# main.net
KiCad netlist of a schematic drawn in EAGLE
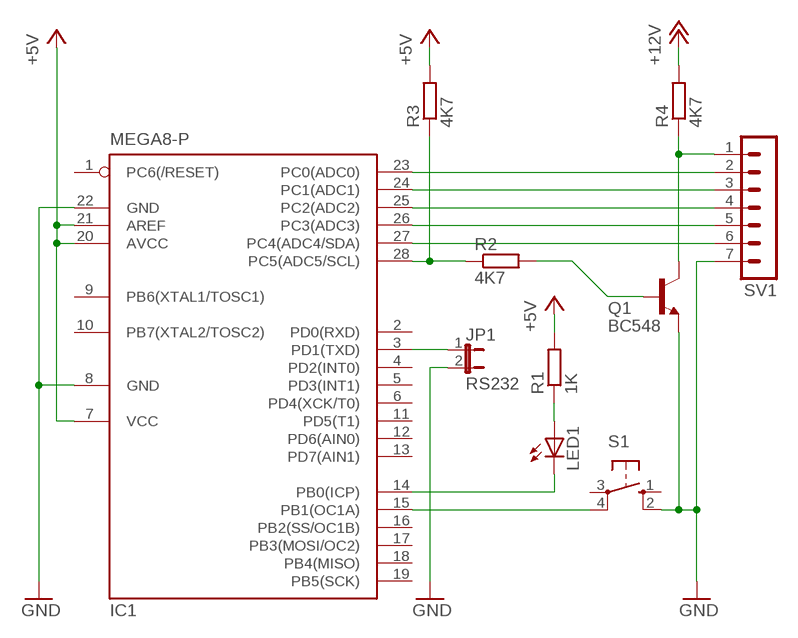
[diagram p0: schematic, sheet 1]
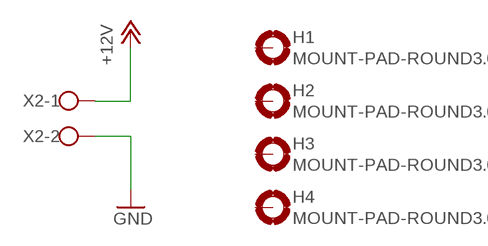
[diagram p1: schematic, sheet 2]
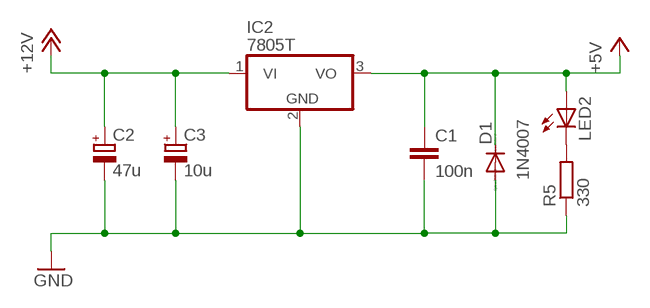
[diagram p2: schematic, sheet 3]

(export (version "E")
  (design (tool "Eeschema 10.0.6"))
  (components
    (comp (ref "IC1")
      (value "MEGA8-P")
      (footprint "eagle-import:DIL28-3")
      (libsource (lib "eagle-import") (part "MEGA8-P"))
    )
    (comp (ref "JP1")
      (value "RS232")
      (footprint "eagle-import:JP1")
      (libsource (lib "eagle-import") (part "JP1E"))
    )
    (comp (ref "LED1")
      (value "LED5MM")
      (footprint "eagle-import:LED5MM")
      (libsource (lib "eagle-import") (part "LED5MM"))
    )
    (comp (ref "Q1")
      (value "BC548")
      (footprint "eagle-import:TO92-EBC")
      (libsource (lib "eagle-import") (part "BC548"))
    )
    (comp (ref "R1")
      (value "1K")
      (footprint "eagle-import:0204_7")
      (libsource (lib "eagle-import") (part "R-EU_0204/7"))
    )
    (comp (ref "R2")
      (value "4K7")
      (footprint "eagle-import:0204_7")
      (libsource (lib "eagle-import") (part "R-EU_0204/7"))
    )
    (comp (ref "R3")
      (value "4K7")
      (footprint "eagle-import:0204_7")
      (libsource (lib "eagle-import") (part "R-EU_0204/7"))
    )
    (comp (ref "R4")
      (value "4K7")
      (footprint "eagle-import:0204_7")
      (libsource (lib "eagle-import") (part "R-EU_0204/7"))
    )
    (comp (ref "S1")
      (value "40-XX")
      (footprint "eagle-import:B3F-40XX")
      (fields (field (name "MF") "OMRON COMPONENTS USA") (field (name "MPN") "B3F-4000"))
      (libsource (lib "eagle-import") (part "40-XX"))
    )
    (comp (ref "SV1")
      (value "MA07-1")
      (footprint "eagle-import:MA07-1")
      (libsource (lib "eagle-import") (part "MA07-1"))
    )
    (comp (ref "H1")
      (value "MOUNT-PAD-ROUND3.0")
      (footprint "eagle-import:3,0-PAD")
      (libsource (lib "eagle-import") (part "MOUNT-PAD-ROUND3.0"))
    )
    (comp (ref "H2")
      (value "MOUNT-PAD-ROUND3.0")
      (footprint "eagle-import:3,0-PAD")
      (libsource (lib "eagle-import") (part "MOUNT-PAD-ROUND3.0"))
    )
    (comp (ref "H3")
      (value "MOUNT-PAD-ROUND3.0")
      (footprint "eagle-import:3,0-PAD")
      (libsource (lib "eagle-import") (part "MOUNT-PAD-ROUND3.0"))
    )
    (comp (ref "H4")
      (value "MOUNT-PAD-ROUND3.0")
      (footprint "eagle-import:3,0-PAD")
      (libsource (lib "eagle-import") (part "MOUNT-PAD-ROUND3.0"))
    )
    (comp (ref "X2")
      (value "W237-102")
      (footprint "eagle-import:W237-102")
      (fields (field (name "MPN") "237-102"))
      (libsource (lib "eagle-import") (part "W237-102"))
    )
    (comp (ref "C1")
      (value "100n")
      (footprint "eagle-import:C025-025X050")
      (libsource (lib "eagle-import") (part "C-EU025-025X050"))
    )
    (comp (ref "C2")
      (value "47u")
      (footprint "eagle-import:E2,5-6")
      (libsource (lib "eagle-import") (part "CPOL-EUE2.5-6"))
    )
    (comp (ref "C3")
      (value "10u")
      (footprint "eagle-import:E2,5-6")
      (libsource (lib "eagle-import") (part "CPOL-EUE2.5-6"))
    )
    (comp (ref "D1")
      (value "1N4007")
      (footprint "eagle-import:D-7.5")
      (libsource (lib "eagle-import") (part "DIODE-D-7.5"))
    )
    (comp (ref "IC2")
      (value "7805T")
      (footprint "eagle-import:TO220H")
      (libsource (lib "eagle-import") (part "78T05"))
    )
    (comp (ref "LED2")
      (value "LED5MM")
      (footprint "eagle-import:LED5MM")
      (libsource (lib "eagle-import") (part "LED5MM"))
    )
    (comp (ref "R5")
      (value "330")
      (footprint "eagle-import:0204_7")
      (libsource (lib "eagle-import") (part "resistor_R-EU_0204/7"))
    )
  )
  (nets
    (net (code "1") (name "+5V") (class "Default")
      (node (ref "C1") (pin "1") (pinfunction "1_1") (pintype "passive"))
      (node (ref "D1") (pin "C") (pinfunction "C_C") (pintype "passive"))
      (node (ref "IC1") (pin "20") (pinfunction "AVCC_20") (pintype "power_in"))
      (node (ref "IC1") (pin "21") (pinfunction "AREF_21") (pintype "passive"))
      (node (ref "IC1") (pin "7") (pinfunction "VCC_7") (pintype "power_in"))
      (node (ref "IC2") (pin "3") (pinfunction "VO_3") (pintype "passive"))
      (node (ref "LED2") (pin "A") (pinfunction "A_A") (pintype "passive"))
      (node (ref "R1") (pin "2") (pinfunction "2_2") (pintype "passive"))
      (node (ref "R3") (pin "2") (pinfunction "2_2") (pintype "passive"))
    )
    (net (code "2") (name "+12V") (class "Default")
      (node (ref "C2") (pin "+") (pinfunction "+_+") (pintype "passive"))
      (node (ref "C3") (pin "+") (pinfunction "+_+") (pintype "passive"))
      (node (ref "IC2") (pin "1") (pinfunction "VI_1") (pintype "input"))
      (node (ref "R4") (pin "2") (pinfunction "2_2") (pintype "passive"))
      (node (ref "X2") (pin "1") (pinfunction "KL_1") (pintype "passive"))
    )
    (net (code "3") (name "GND") (class "Default")
      (node (ref "C1") (pin "2") (pinfunction "2_2") (pintype "passive"))
      (node (ref "C2") (pin "-") (pinfunction "-_-") (pintype "passive"))
      (node (ref "C3") (pin "-") (pinfunction "-_-") (pintype "passive"))
      (node (ref "D1") (pin "A") (pinfunction "A_A") (pintype "passive"))
      (node (ref "IC1") (pin "22") (pinfunction "GND_22") (pintype "power_in"))
      (node (ref "IC1") (pin "8") (pinfunction "GND_8") (pintype "power_in"))
      (node (ref "IC2") (pin "2") (pinfunction "GND_2") (pintype "passive"))
      (node (ref "JP1") (pin "2") (pinfunction "2_2") (pintype "passive"))
      (node (ref "Q1") (pin "E") (pinfunction "E_E") (pintype "passive"))
      (node (ref "R5") (pin "1") (pinfunction "1_1") (pintype "passive"))
      (node (ref "S1") (pin "2") (pinfunction "S1_2") (pintype "passive"))
      (node (ref "SV1") (pin "7") (pinfunction "7_7") (pintype "passive"))
      (node (ref "X2") (pin "2") (pinfunction "KL_2") (pintype "passive"))
    )
    (net (code "4") (name "Net-(IC1-PB0(ICP))") (class "Default")
      (node (ref "IC1") (pin "14") (pinfunction "PB0(ICP)_14") (pintype "bidirectional"))
      (node (ref "LED1") (pin "K") (pinfunction "C_K") (pintype "passive"))
    )
    (net (code "5") (name "Net-(IC1-PB1(OC1A))") (class "Default")
      (node (ref "IC1") (pin "15") (pinfunction "PB1(OC1A)_15") (pintype "bidirectional"))
      (node (ref "S1") (pin "4") (pinfunction "P1_4") (pintype "passive"))
    )
    (net (code "6") (name "Net-(IC1-PC0(ADC0))") (class "Default")
      (node (ref "IC1") (pin "23") (pinfunction "PC0(ADC0)_23") (pintype "bidirectional"))
      (node (ref "SV1") (pin "2") (pinfunction "2_2") (pintype "passive"))
    )
    (net (code "7") (name "Net-(IC1-PC1(ADC1))") (class "Default")
      (node (ref "IC1") (pin "24") (pinfunction "PC1(ADC1)_24") (pintype "bidirectional"))
      (node (ref "SV1") (pin "3") (pinfunction "3_3") (pintype "passive"))
    )
    (net (code "8") (name "Net-(IC1-PC2(ADC2))") (class "Default")
      (node (ref "IC1") (pin "25") (pinfunction "PC2(ADC2)_25") (pintype "bidirectional"))
      (node (ref "SV1") (pin "4") (pinfunction "4_4") (pintype "passive"))
    )
    (net (code "9") (name "Net-(IC1-PC3(ADC3))") (class "Default")
      (node (ref "IC1") (pin "26") (pinfunction "PC3(ADC3)_26") (pintype "bidirectional"))
      (node (ref "SV1") (pin "5") (pinfunction "5_5") (pintype "passive"))
    )
    (net (code "10") (name "Net-(IC1-PC4(ADC4{slash}SDA))") (class "Default")
      (node (ref "IC1") (pin "27") (pinfunction "PC4(ADC4/SDA)_27") (pintype "bidirectional"))
      (node (ref "SV1") (pin "6") (pinfunction "6_6") (pintype "passive"))
    )
    (net (code "11") (name "Net-(IC1-PC5(ADC5{slash}SCL))") (class "Default")
      (node (ref "IC1") (pin "28") (pinfunction "PC5(ADC5/SCL)_28") (pintype "bidirectional"))
      (node (ref "R2") (pin "1") (pinfunction "1_1") (pintype "passive"))
      (node (ref "R3") (pin "1") (pinfunction "1_1") (pintype "passive"))
    )
    (net (code "12") (name "Net-(IC1-PD1(TXD))") (class "Default")
      (node (ref "IC1") (pin "3") (pinfunction "PD1(TXD)_3") (pintype "bidirectional"))
      (node (ref "JP1") (pin "1") (pinfunction "1_1") (pintype "passive"))
    )
    (net (code "13") (name "Net-(LED1-PadA)") (class "Default")
      (node (ref "LED1") (pin "A") (pinfunction "A_A") (pintype "passive"))
      (node (ref "R1") (pin "1") (pinfunction "1_1") (pintype "passive"))
    )
    (net (code "14") (name "Net-(LED2-C)") (class "Default")
      (node (ref "LED2") (pin "K") (pinfunction "C_K") (pintype "passive"))
      (node (ref "R5") (pin "2") (pinfunction "2_2") (pintype "passive"))
    )
    (net (code "15") (name "Net-(Q1-PadB)") (class "Default")
      (node (ref "Q1") (pin "B") (pinfunction "B_B") (pintype "passive"))
      (node (ref "R2") (pin "2") (pinfunction "2_2") (pintype "passive"))
    )
    (net (code "16") (name "Net-(Q1-PadC)") (class "Default")
      (node (ref "Q1") (pin "C") (pinfunction "C_C") (pintype "passive"))
      (node (ref "R4") (pin "1") (pinfunction "1_1") (pintype "passive"))
      (node (ref "SV1") (pin "1") (pinfunction "1_1") (pintype "passive"))
    )
    (net (code "17") (name "unconnected-(H1-MOUNT-PadB3,0)") (class "Default")
      (node (ref "H1") (pin "B3,0") (pinfunction "MOUNT_B3,0") (pintype "passive"))
    )
    (net (code "18") (name "unconnected-(H2-MOUNT-PadB3,0)") (class "Default")
      (node (ref "H2") (pin "B3,0") (pinfunction "MOUNT_B3,0") (pintype "passive"))
    )
    (net (code "19") (name "unconnected-(H3-MOUNT-PadB3,0)") (class "Default")
      (node (ref "H3") (pin "B3,0") (pinfunction "MOUNT_B3,0") (pintype "passive"))
    )
    (net (code "20") (name "unconnected-(H4-MOUNT-PadB3,0)") (class "Default")
      (node (ref "H4") (pin "B3,0") (pinfunction "MOUNT_B3,0") (pintype "passive"))
    )
    (net (code "21") (name "unconnected-(IC1-PB2(SS{slash}OC1B)-Pad16)") (class "Default")
      (node (ref "IC1") (pin "16") (pinfunction "PB2(SS/OC1B)_16") (pintype "bidirectional"))
    )
    (net (code "22") (name "unconnected-(IC1-PB3(MOSI{slash}OC2)-Pad17)") (class "Default")
      (node (ref "IC1") (pin "17") (pinfunction "PB3(MOSI/OC2)_17") (pintype "bidirectional"))
    )
    (net (code "23") (name "unconnected-(IC1-PB4(MISO)-Pad18)") (class "Default")
      (node (ref "IC1") (pin "18") (pinfunction "PB4(MISO)_18") (pintype "bidirectional"))
    )
    (net (code "24") (name "unconnected-(IC1-PB5(SCK)-Pad19)") (class "Default")
      (node (ref "IC1") (pin "19") (pinfunction "PB5(SCK)_19") (pintype "bidirectional"))
    )
    (net (code "25") (name "unconnected-(IC1-PB6(XTAL1{slash}TOSC1)-Pad9)") (class "Default")
      (node (ref "IC1") (pin "9") (pinfunction "PB6(XTAL1/TOSC1)_9") (pintype "bidirectional"))
    )
    (net (code "26") (name "unconnected-(IC1-PB7(XTAL2{slash}TOSC2)-Pad10)") (class "Default")
      (node (ref "IC1") (pin "10") (pinfunction "PB7(XTAL2/TOSC2)_10") (pintype "bidirectional"))
    )
    (net (code "27") (name "unconnected-(IC1-PC6({slash}RESET)-Pad1)") (class "Default")
      (node (ref "IC1") (pin "1") (pinfunction "PC6(/RESET)_1") (pintype "bidirectional"))
    )
    (net (code "28") (name "unconnected-(IC1-PD0(RXD)-Pad2)") (class "Default")
      (node (ref "IC1") (pin "2") (pinfunction "PD0(RXD)_2") (pintype "bidirectional"))
    )
    (net (code "29") (name "unconnected-(IC1-PD2(INT0)-Pad4)") (class "Default")
      (node (ref "IC1") (pin "4") (pinfunction "PD2(INT0)_4") (pintype "bidirectional"))
    )
    (net (code "30") (name "unconnected-(IC1-PD3(INT1)-Pad5)") (class "Default")
      (node (ref "IC1") (pin "5") (pinfunction "PD3(INT1)_5") (pintype "bidirectional"))
    )
    (net (code "31") (name "unconnected-(IC1-PD4(XCK{slash}T0)-Pad6)") (class "Default")
      (node (ref "IC1") (pin "6") (pinfunction "PD4(XCK/T0)_6") (pintype "bidirectional"))
    )
    (net (code "32") (name "unconnected-(IC1-PD5(T1)-Pad11)") (class "Default")
      (node (ref "IC1") (pin "11") (pinfunction "PD5(T1)_11") (pintype "bidirectional"))
    )
    (net (code "33") (name "unconnected-(IC1-PD6(AIN0)-Pad12)") (class "Default")
      (node (ref "IC1") (pin "12") (pinfunction "PD6(AIN0)_12") (pintype "bidirectional"))
    )
    (net (code "34") (name "unconnected-(IC1-PD7(AIN1)-Pad13)") (class "Default")
      (node (ref "IC1") (pin "13") (pinfunction "PD7(AIN1)_13") (pintype "bidirectional"))
    )
    (net (code "35") (name "unconnected-(S1-P-Pad3)") (class "Default")
      (node (ref "S1") (pin "3") (pinfunction "P_3") (pintype "passive"))
    )
    (net (code "36") (name "unconnected-(S1-S-Pad1)") (class "Default")
      (node (ref "S1") (pin "1") (pinfunction "S_1") (pintype "passive"))
    )
  )
)
